# 7006268-1.net
KiCad netlist of a schematic drawn in EAGLE
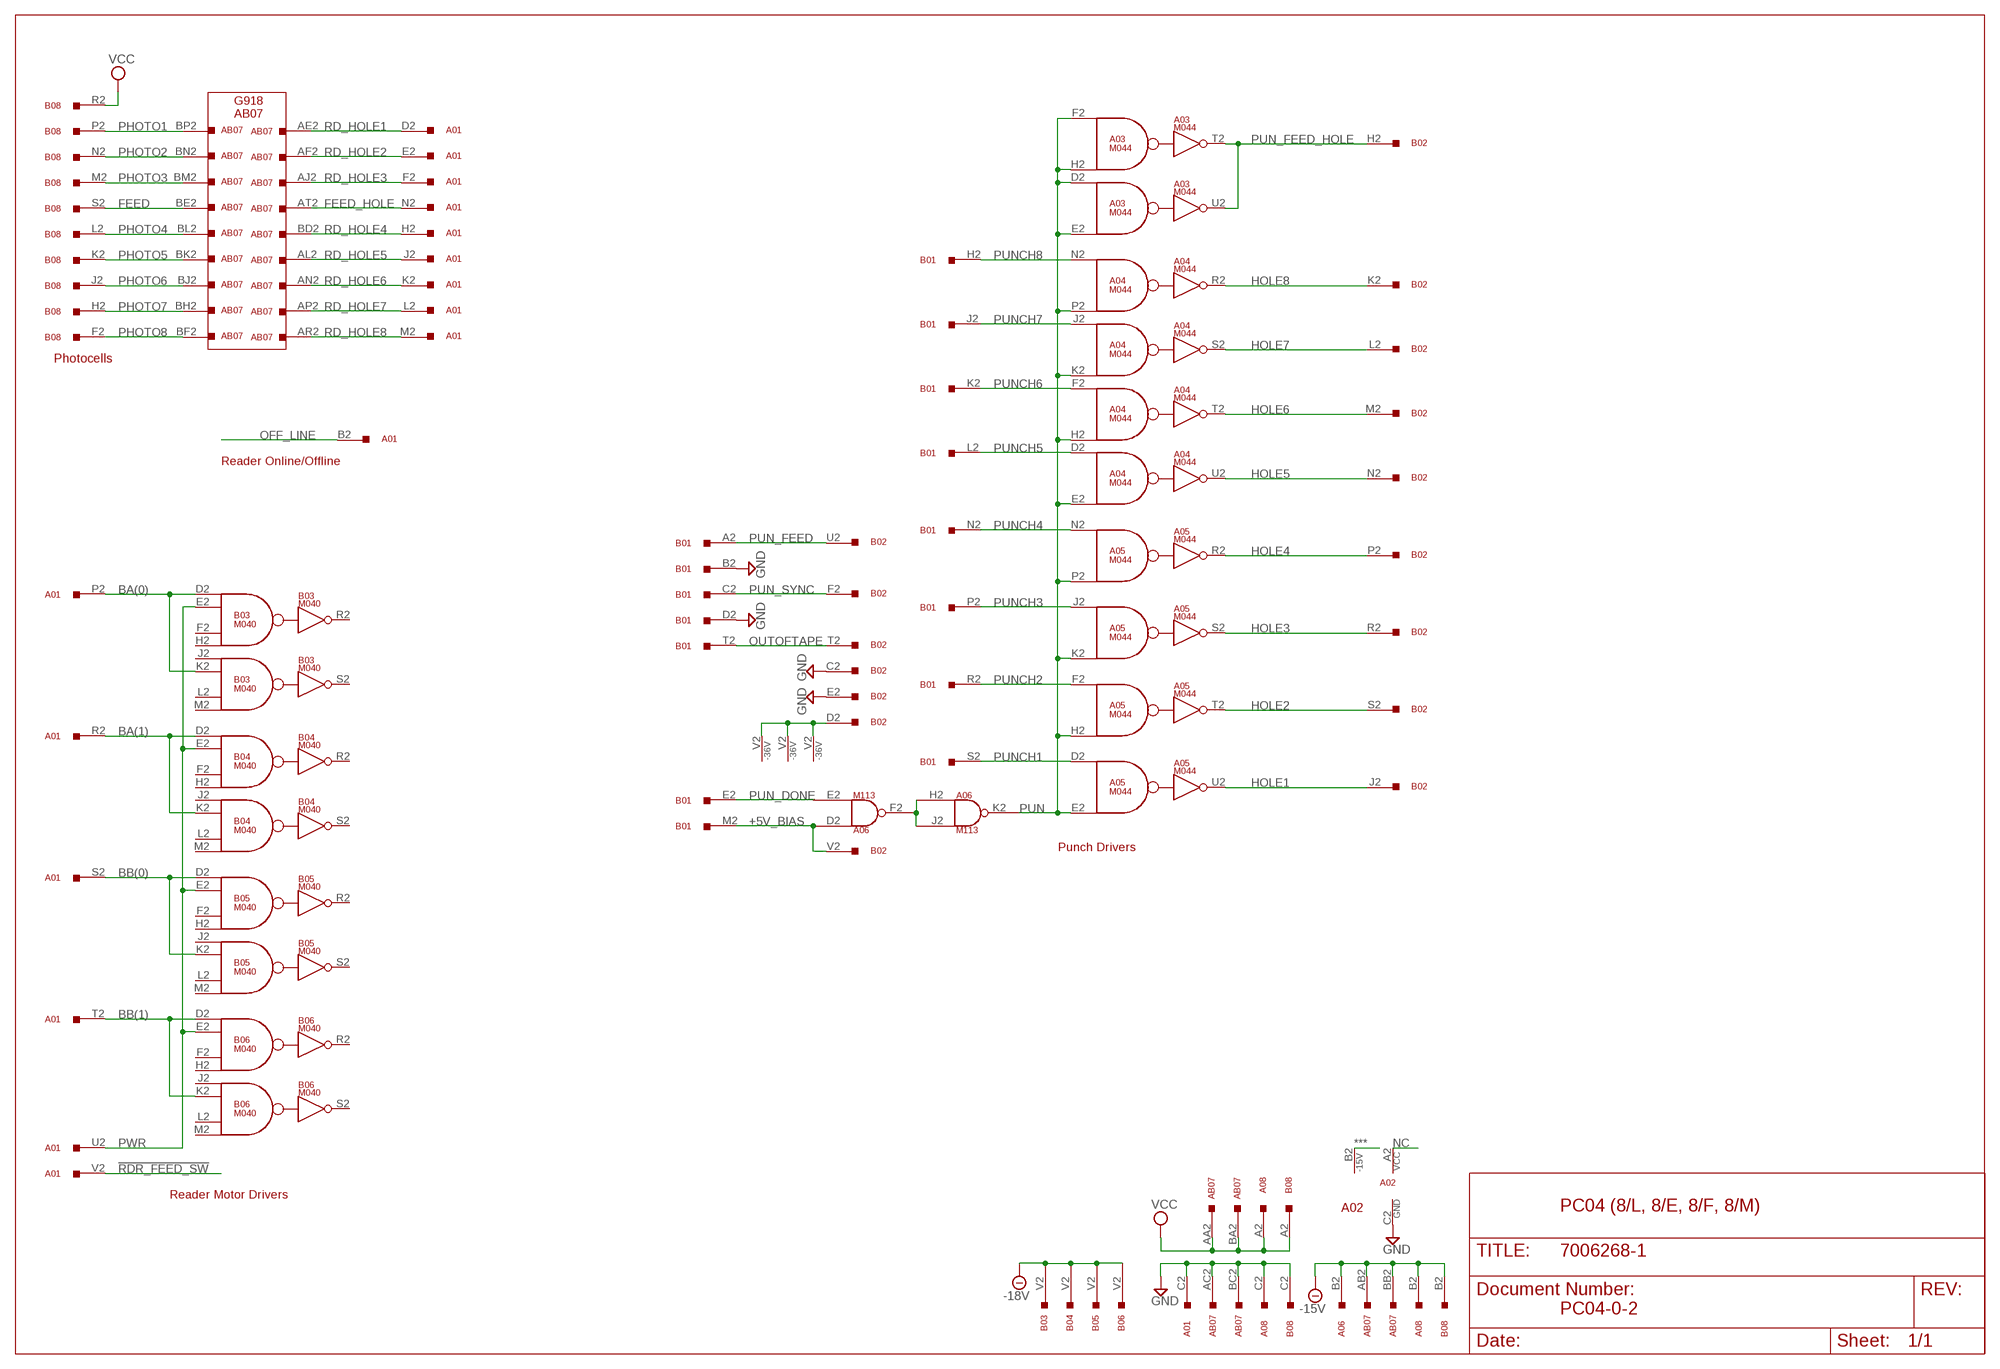
[diagram p0: schematic, sheet 1]

(export (version "E")
  (design (tool "Eeschema 10.0.6"))
  (components
    (comp (ref "A01")
      (value "W033")
      (footprint "eagle-import:H807")
      (libsource (lib "eagle-import") (part "W023"))
    )
    (comp (ref "A02")
      (value "EMPTY")
      (footprint "eagle-import:H807")
      (libsource (lib "eagle-import") (part "EMPTY"))
    )
    (comp (ref "A03")
      (value "M044")
      (footprint "eagle-import:H807")
      (libsource (lib "eagle-import") (part "M044"))
    )
    (comp (ref "A04")
      (value "M044")
      (footprint "eagle-import:H807")
      (libsource (lib "eagle-import") (part "M044"))
    )
    (comp (ref "A05")
      (value "M044")
      (footprint "eagle-import:H807")
      (libsource (lib "eagle-import") (part "M044"))
    )
    (comp (ref "A06")
      (value "M113")
      (footprint "eagle-import:H807")
      (libsource (lib "eagle-import") (part "M113"))
    )
    (comp (ref "A08")
      (value "W033")
      (footprint "eagle-import:H807")
      (libsource (lib "eagle-import") (part "W023"))
    )
    (comp (ref "AB07")
      (value "G918")
      (footprint "eagle-import:H807-2")
      (libsource (lib "eagle-import") (part "W991"))
    )
    (comp (ref "B01")
      (value "W033")
      (footprint "eagle-import:H807")
      (libsource (lib "eagle-import") (part "W023"))
    )
    (comp (ref "B02")
      (value "W033")
      (footprint "eagle-import:H807")
      (libsource (lib "eagle-import") (part "W023"))
    )
    (comp (ref "B03")
      (value "M040")
      (footprint "eagle-import:H807")
      (libsource (lib "eagle-import") (part "M040"))
    )
    (comp (ref "B04")
      (value "M040")
      (footprint "eagle-import:H807")
      (libsource (lib "eagle-import") (part "M040"))
    )
    (comp (ref "B05")
      (value "M040")
      (footprint "eagle-import:H807")
      (libsource (lib "eagle-import") (part "M040"))
    )
    (comp (ref "B06")
      (value "M040")
      (footprint "eagle-import:H807")
      (libsource (lib "eagle-import") (part "M040"))
    )
    (comp (ref "B08")
      (value "W033")
      (footprint "eagle-import:H807")
      (libsource (lib "eagle-import") (part "W023"))
    )
  )
  (nets
    (net (code "1") (name "-15V") (class "Default")
      (node (ref "A06") (pin "B2") (pinfunction "P$2_B2") (pintype "bidirectional"))
      (node (ref "A08") (pin "B2") (pinfunction "P$2_B2") (pintype "bidirectional"))
      (node (ref "AB07") (pin "AB2") (pinfunction "P$2_AB2") (pintype "bidirectional"))
      (node (ref "AB07") (pin "BB2") (pinfunction "P$2_BB2") (pintype "bidirectional"))
      (node (ref "B08") (pin "B2") (pinfunction "P$2_B2") (pintype "bidirectional"))
    )
    (net (code "2") (name "-18V") (class "Default")
      (node (ref "B03") (pin "V2") (pinfunction "P$1_V2") (pintype "input"))
      (node (ref "B04") (pin "V2") (pinfunction "P$1_V2") (pintype "input"))
      (node (ref "B05") (pin "V2") (pinfunction "P$1_V2") (pintype "input"))
      (node (ref "B06") (pin "V2") (pinfunction "P$1_V2") (pintype "input"))
    )
    (net (code "3") (name "/***") (class "Default")
      (node (ref "A02") (pin "B2") (pinfunction "-15V_B2") (pintype "power_in"))
    )
    (net (code "4") (name "/+5V_BIAS") (class "Default")
      (node (ref "A06") (pin "D2") (pinfunction "IN1_D2") (pintype "input"))
      (node (ref "B01") (pin "M2") (pinfunction "P$2_M2") (pintype "bidirectional"))
      (node (ref "B02") (pin "V2") (pinfunction "P$2_V2") (pintype "bidirectional"))
    )
    (net (code "5") (name "/BA(0)") (class "Default")
      (node (ref "A01") (pin "P2") (pinfunction "P$2_P2") (pintype "bidirectional"))
      (node (ref "B03") (pin "D2") (pinfunction "D_D2") (pintype "input"))
      (node (ref "B03") (pin "K2") (pinfunction "E_K2") (pintype "input"))
    )
    (net (code "6") (name "/BA(1)") (class "Default")
      (node (ref "A01") (pin "R2") (pinfunction "P$2_R2") (pintype "bidirectional"))
      (node (ref "B04") (pin "D2") (pinfunction "D_D2") (pintype "input"))
      (node (ref "B04") (pin "K2") (pinfunction "E_K2") (pintype "input"))
    )
    (net (code "7") (name "/BB(0)") (class "Default")
      (node (ref "A01") (pin "S2") (pinfunction "P$2_S2") (pintype "bidirectional"))
      (node (ref "B05") (pin "D2") (pinfunction "D_D2") (pintype "input"))
      (node (ref "B05") (pin "K2") (pinfunction "E_K2") (pintype "input"))
    )
    (net (code "8") (name "/BB(1)") (class "Default")
      (node (ref "A01") (pin "T2") (pinfunction "P$2_T2") (pintype "bidirectional"))
      (node (ref "B06") (pin "D2") (pinfunction "D_D2") (pintype "input"))
      (node (ref "B06") (pin "K2") (pinfunction "E_K2") (pintype "input"))
    )
    (net (code "9") (name "/FEED") (class "Default")
      (node (ref "AB07") (pin "BE2") (pinfunction "P$2_BE2") (pintype "bidirectional"))
      (node (ref "B08") (pin "S2") (pinfunction "P$2_S2") (pintype "bidirectional"))
    )
    (net (code "10") (name "/FEED_HOLE") (class "Default")
      (node (ref "A01") (pin "N2") (pinfunction "P$2_N2") (pintype "bidirectional"))
      (node (ref "AB07") (pin "AT2") (pinfunction "P$2_AT2") (pintype "bidirectional"))
    )
    (net (code "11") (name "/HOLE1") (class "Default")
      (node (ref "A05") (pin "U2") (pinfunction "R_U2") (pintype "open_collector"))
      (node (ref "B02") (pin "J2") (pinfunction "P$2_J2") (pintype "bidirectional"))
    )
    (net (code "12") (name "/HOLE2") (class "Default")
      (node (ref "A05") (pin "T2") (pinfunction "R_T2") (pintype "open_collector"))
      (node (ref "B02") (pin "S2") (pinfunction "P$2_S2") (pintype "bidirectional"))
    )
    (net (code "13") (name "/HOLE3") (class "Default")
      (node (ref "A05") (pin "S2") (pinfunction "R_S2") (pintype "open_collector"))
      (node (ref "B02") (pin "R2") (pinfunction "P$2_R2") (pintype "bidirectional"))
    )
    (net (code "14") (name "/HOLE4") (class "Default")
      (node (ref "A05") (pin "R2") (pinfunction "R_R2") (pintype "open_collector"))
      (node (ref "B02") (pin "P2") (pinfunction "P$2_P2") (pintype "bidirectional"))
    )
    (net (code "15") (name "/HOLE5") (class "Default")
      (node (ref "A04") (pin "U2") (pinfunction "R_U2") (pintype "open_collector"))
      (node (ref "B02") (pin "N2") (pinfunction "P$2_N2") (pintype "bidirectional"))
    )
    (net (code "16") (name "/HOLE6") (class "Default")
      (node (ref "A04") (pin "T2") (pinfunction "R_T2") (pintype "open_collector"))
      (node (ref "B02") (pin "M2") (pinfunction "P$2_M2") (pintype "bidirectional"))
    )
    (net (code "17") (name "/HOLE7") (class "Default")
      (node (ref "A04") (pin "S2") (pinfunction "R_S2") (pintype "open_collector"))
      (node (ref "B02") (pin "L2") (pinfunction "P$2_L2") (pintype "bidirectional"))
    )
    (net (code "18") (name "/HOLE8") (class "Default")
      (node (ref "A04") (pin "R2") (pinfunction "R_R2") (pintype "open_collector"))
      (node (ref "B02") (pin "K2") (pinfunction "P$2_K2") (pintype "bidirectional"))
    )
    (net (code "19") (name "/NC") (class "Default")
      (node (ref "A02") (pin "A2") (pinfunction "VCC_A2") (pintype "power_in"))
    )
    (net (code "20") (name "/OFF_LINE") (class "Default")
      (node (ref "A01") (pin "B2") (pinfunction "P$2_B2") (pintype "bidirectional"))
    )
    (net (code "21") (name "/OUTOFTAPE") (class "Default")
      (node (ref "B01") (pin "T2") (pinfunction "P$2_T2") (pintype "bidirectional"))
      (node (ref "B02") (pin "T2") (pinfunction "P$2_T2") (pintype "bidirectional"))
    )
    (net (code "22") (name "/PHOTO1") (class "Default")
      (node (ref "AB07") (pin "BP2") (pinfunction "P$2_BP2") (pintype "bidirectional"))
      (node (ref "B08") (pin "P2") (pinfunction "P$2_P2") (pintype "bidirectional"))
    )
    (net (code "23") (name "/PHOTO2") (class "Default")
      (node (ref "AB07") (pin "BN2") (pinfunction "P$2_BN2") (pintype "bidirectional"))
      (node (ref "B08") (pin "N2") (pinfunction "P$2_N2") (pintype "bidirectional"))
    )
    (net (code "24") (name "/PHOTO3") (class "Default")
      (node (ref "AB07") (pin "BM2") (pinfunction "P$2_BM2") (pintype "bidirectional"))
      (node (ref "B08") (pin "M2") (pinfunction "P$2_M2") (pintype "bidirectional"))
    )
    (net (code "25") (name "/PHOTO4") (class "Default")
      (node (ref "AB07") (pin "BL2") (pinfunction "P$2_BL2") (pintype "bidirectional"))
      (node (ref "B08") (pin "L2") (pinfunction "P$2_L2") (pintype "bidirectional"))
    )
    (net (code "26") (name "/PHOTO5") (class "Default")
      (node (ref "AB07") (pin "BK2") (pinfunction "P$2_BK2") (pintype "bidirectional"))
      (node (ref "B08") (pin "K2") (pinfunction "P$2_K2") (pintype "bidirectional"))
    )
    (net (code "27") (name "/PHOTO6") (class "Default")
      (node (ref "AB07") (pin "BJ2") (pinfunction "P$2_BJ2") (pintype "bidirectional"))
      (node (ref "B08") (pin "J2") (pinfunction "P$2_J2") (pintype "bidirectional"))
    )
    (net (code "28") (name "/PHOTO7") (class "Default")
      (node (ref "AB07") (pin "BH2") (pinfunction "P$2_BH2") (pintype "bidirectional"))
      (node (ref "B08") (pin "H2") (pinfunction "P$2_H2") (pintype "bidirectional"))
    )
    (net (code "29") (name "/PHOTO8") (class "Default")
      (node (ref "AB07") (pin "BF2") (pinfunction "P$2_BF2") (pintype "bidirectional"))
      (node (ref "B08") (pin "F2") (pinfunction "P$2_F2") (pintype "bidirectional"))
    )
    (net (code "30") (name "/PUN") (class "Default")
      (node (ref "A03") (pin "D2") (pinfunction "D_D2") (pintype "input"))
      (node (ref "A03") (pin "E2") (pinfunction "H_E2") (pintype "input"))
      (node (ref "A03") (pin "F2") (pinfunction "D_F2") (pintype "input"))
      (node (ref "A03") (pin "H2") (pinfunction "H_H2") (pintype "input"))
      (node (ref "A04") (pin "E2") (pinfunction "H_E2") (pintype "input"))
      (node (ref "A04") (pin "H2") (pinfunction "H_H2") (pintype "input"))
      (node (ref "A04") (pin "K2") (pinfunction "H_K2") (pintype "input"))
      (node (ref "A04") (pin "P2") (pinfunction "H_P2") (pintype "input"))
      (node (ref "A05") (pin "E2") (pinfunction "H_E2") (pintype "input"))
      (node (ref "A05") (pin "H2") (pinfunction "H_H2") (pintype "input"))
      (node (ref "A05") (pin "K2") (pinfunction "H_K2") (pintype "input"))
      (node (ref "A05") (pin "P2") (pinfunction "H_P2") (pintype "input"))
      (node (ref "A06") (pin "K2") (pinfunction "OUT_K2") (pintype "output"))
    )
    (net (code "31") (name "/PUNCH1") (class "Default")
      (node (ref "A05") (pin "D2") (pinfunction "D_D2") (pintype "input"))
      (node (ref "B01") (pin "S2") (pinfunction "P$2_S2") (pintype "bidirectional"))
    )
    (net (code "32") (name "/PUNCH2") (class "Default")
      (node (ref "A05") (pin "F2") (pinfunction "D_F2") (pintype "input"))
      (node (ref "B01") (pin "R2") (pinfunction "P$2_R2") (pintype "bidirectional"))
    )
    (net (code "33") (name "/PUNCH3") (class "Default")
      (node (ref "A05") (pin "J2") (pinfunction "D_J2") (pintype "input"))
      (node (ref "B01") (pin "P2") (pinfunction "P$2_P2") (pintype "bidirectional"))
    )
    (net (code "34") (name "/PUNCH4") (class "Default")
      (node (ref "A05") (pin "N2") (pinfunction "D_N2") (pintype "input"))
      (node (ref "B01") (pin "N2") (pinfunction "P$2_N2") (pintype "bidirectional"))
    )
    (net (code "35") (name "/PUNCH5") (class "Default")
      (node (ref "A04") (pin "D2") (pinfunction "D_D2") (pintype "input"))
      (node (ref "B01") (pin "L2") (pinfunction "P$2_L2") (pintype "bidirectional"))
    )
    (net (code "36") (name "/PUNCH6") (class "Default")
      (node (ref "A04") (pin "F2") (pinfunction "D_F2") (pintype "input"))
      (node (ref "B01") (pin "K2") (pinfunction "P$2_K2") (pintype "bidirectional"))
    )
    (net (code "37") (name "/PUNCH7") (class "Default")
      (node (ref "A04") (pin "J2") (pinfunction "D_J2") (pintype "input"))
      (node (ref "B01") (pin "J2") (pinfunction "P$2_J2") (pintype "bidirectional"))
    )
    (net (code "38") (name "/PUNCH8") (class "Default")
      (node (ref "A04") (pin "N2") (pinfunction "D_N2") (pintype "input"))
      (node (ref "B01") (pin "H2") (pinfunction "P$2_H2") (pintype "bidirectional"))
    )
    (net (code "39") (name "/PUN_DONE") (class "Default")
      (node (ref "A06") (pin "E2") (pinfunction "IN2_E2") (pintype "input"))
      (node (ref "B01") (pin "E2") (pinfunction "P$2_E2") (pintype "bidirectional"))
    )
    (net (code "40") (name "/PUN_FEED") (class "Default")
      (node (ref "B01") (pin "A2") (pinfunction "P$2_A2") (pintype "bidirectional"))
      (node (ref "B02") (pin "U2") (pinfunction "P$2_U2") (pintype "bidirectional"))
    )
    (net (code "41") (name "/PUN_FEED_HOLE") (class "Default")
      (node (ref "A03") (pin "T2") (pinfunction "R_T2") (pintype "open_collector"))
      (node (ref "A03") (pin "U2") (pinfunction "R_U2") (pintype "open_collector"))
      (node (ref "B02") (pin "H2") (pinfunction "P$2_H2") (pintype "bidirectional"))
    )
    (net (code "42") (name "/PUN_SYNC") (class "Default")
      (node (ref "B01") (pin "C2") (pinfunction "P$2_C2") (pintype "bidirectional"))
      (node (ref "B02") (pin "F2") (pinfunction "P$2_F2") (pintype "bidirectional"))
    )
    (net (code "43") (name "/PWR") (class "Default")
      (node (ref "A01") (pin "U2") (pinfunction "P$2_U2") (pintype "bidirectional"))
      (node (ref "B03") (pin "E2") (pinfunction "E_E2") (pintype "input"))
      (node (ref "B04") (pin "E2") (pinfunction "E_E2") (pintype "input"))
      (node (ref "B05") (pin "E2") (pinfunction "E_E2") (pintype "input"))
      (node (ref "B06") (pin "E2") (pinfunction "E_E2") (pintype "input"))
    )
    (net (code "44") (name "/RD_HOLE1") (class "Default")
      (node (ref "A01") (pin "D2") (pinfunction "P$2_D2") (pintype "bidirectional"))
      (node (ref "AB07") (pin "AE2") (pinfunction "P$2_AE2") (pintype "bidirectional"))
    )
    (net (code "45") (name "/RD_HOLE2") (class "Default")
      (node (ref "A01") (pin "E2") (pinfunction "P$2_E2") (pintype "bidirectional"))
      (node (ref "AB07") (pin "AF2") (pinfunction "P$2_AF2") (pintype "bidirectional"))
    )
    (net (code "46") (name "/RD_HOLE3") (class "Default")
      (node (ref "A01") (pin "F2") (pinfunction "P$2_F2") (pintype "bidirectional"))
      (node (ref "AB07") (pin "AJ2") (pinfunction "P$2_AJ2") (pintype "bidirectional"))
    )
    (net (code "47") (name "/RD_HOLE4") (class "Default")
      (node (ref "A01") (pin "H2") (pinfunction "P$2_H2") (pintype "bidirectional"))
      (node (ref "AB07") (pin "BD2") (pinfunction "P$2_BD2") (pintype "bidirectional"))
    )
    (net (code "48") (name "/RD_HOLE5") (class "Default")
      (node (ref "A01") (pin "J2") (pinfunction "P$2_J2") (pintype "bidirectional"))
      (node (ref "AB07") (pin "AL2") (pinfunction "P$2_AL2") (pintype "bidirectional"))
    )
    (net (code "49") (name "/RD_HOLE6") (class "Default")
      (node (ref "A01") (pin "K2") (pinfunction "P$2_K2") (pintype "bidirectional"))
      (node (ref "AB07") (pin "AN2") (pinfunction "P$2_AN2") (pintype "bidirectional"))
    )
    (net (code "50") (name "/RD_HOLE7") (class "Default")
      (node (ref "A01") (pin "L2") (pinfunction "P$2_L2") (pintype "bidirectional"))
      (node (ref "AB07") (pin "AP2") (pinfunction "P$2_AP2") (pintype "bidirectional"))
    )
    (net (code "51") (name "/RD_HOLE8") (class "Default")
      (node (ref "A01") (pin "M2") (pinfunction "P$2_M2") (pintype "bidirectional"))
      (node (ref "AB07") (pin "AR2") (pinfunction "P$2_AR2") (pintype "bidirectional"))
    )
    (net (code "52") (name "/~{RDR_FEED_SW}") (class "Default")
      (node (ref "A01") (pin "V2") (pinfunction "P$2_V2") (pintype "bidirectional"))
    )
    (net (code "53") (name "GND") (class "Default")
      (node (ref "A01") (pin "C2") (pinfunction "P$2_C2") (pintype "bidirectional"))
      (node (ref "A02") (pin "C2") (pinfunction "GND_C2") (pintype "power_in"))
      (node (ref "A08") (pin "C2") (pinfunction "P$2_C2") (pintype "bidirectional"))
      (node (ref "AB07") (pin "AC2") (pinfunction "P$2_AC2") (pintype "bidirectional"))
      (node (ref "AB07") (pin "BC2") (pinfunction "P$2_BC2") (pintype "bidirectional"))
      (node (ref "B01") (pin "B2") (pinfunction "P$2_B2") (pintype "bidirectional"))
      (node (ref "B01") (pin "D2") (pinfunction "P$2_D2") (pintype "bidirectional"))
      (node (ref "B02") (pin "C2") (pinfunction "P$2_C2") (pintype "bidirectional"))
      (node (ref "B02") (pin "E2") (pinfunction "P$2_E2") (pintype "bidirectional"))
      (node (ref "B08") (pin "C2") (pinfunction "P$2_C2") (pintype "bidirectional"))
    )
    (net (code "54") (name "Net-(A03G--36V)") (class "Default")
      (node (ref "A03") (pin "V2") (pinfunction "-36V_V2") (pintype "power_in"))
      (node (ref "A04") (pin "V2") (pinfunction "-36V_V2") (pintype "power_in"))
      (node (ref "A05") (pin "V2") (pinfunction "-36V_V2") (pintype "power_in"))
      (node (ref "B02") (pin "D2") (pinfunction "P$2_D2") (pintype "bidirectional"))
    )
    (net (code "55") (name "Net-(A06D-OUT)") (class "Default")
      (node (ref "A06") (pin "F2") (pinfunction "OUT_F2") (pintype "output"))
      (node (ref "A06") (pin "H2") (pinfunction "IN1_H2") (pintype "input"))
      (node (ref "A06") (pin "J2") (pinfunction "IN2_J2") (pintype "input"))
    )
    (net (code "56") (name "VCC") (class "Default")
      (node (ref "A08") (pin "A2") (pinfunction "P$2_A2") (pintype "bidirectional"))
      (node (ref "AB07") (pin "AA2") (pinfunction "P$2_AA2") (pintype "bidirectional"))
      (node (ref "AB07") (pin "BA2") (pinfunction "P$2_BA2") (pintype "bidirectional"))
      (node (ref "B08") (pin "A2") (pinfunction "P$2_A2") (pintype "bidirectional"))
      (node (ref "B08") (pin "R2") (pinfunction "P$2_R2") (pintype "bidirectional"))
    )
    (net (code "57") (name "unconnected-(B03A-F-PadF2)") (class "Default")
      (node (ref "B03") (pin "F2") (pinfunction "F_F2") (pintype "input"))
    )
    (net (code "58") (name "unconnected-(B03A-H-PadH2)") (class "Default")
      (node (ref "B03") (pin "H2") (pinfunction "H_H2") (pintype "input"))
    )
    (net (code "59") (name "unconnected-(B03A-R-PadR2)") (class "Default")
      (node (ref "B03") (pin "R2") (pinfunction "R_R2") (pintype "open_collector"))
    )
    (net (code "60") (name "unconnected-(B03B-D-PadJ2)") (class "Default")
      (node (ref "B03") (pin "J2") (pinfunction "D_J2") (pintype "input"))
    )
    (net (code "61") (name "unconnected-(B03B-F-PadL2)") (class "Default")
      (node (ref "B03") (pin "L2") (pinfunction "F_L2") (pintype "input"))
    )
    (net (code "62") (name "unconnected-(B03B-H-PadM2)") (class "Default")
      (node (ref "B03") (pin "M2") (pinfunction "H_M2") (pintype "input"))
    )
    (net (code "63") (name "unconnected-(B03B-R-PadS2)") (class "Default")
      (node (ref "B03") (pin "S2") (pinfunction "R_S2") (pintype "open_collector"))
    )
    (net (code "64") (name "unconnected-(B04A-F-PadF2)") (class "Default")
      (node (ref "B04") (pin "F2") (pinfunction "F_F2") (pintype "input"))
    )
    (net (code "65") (name "unconnected-(B04A-H-PadH2)") (class "Default")
      (node (ref "B04") (pin "H2") (pinfunction "H_H2") (pintype "input"))
    )
    (net (code "66") (name "unconnected-(B04A-R-PadR2)") (class "Default")
      (node (ref "B04") (pin "R2") (pinfunction "R_R2") (pintype "open_collector"))
    )
    (net (code "67") (name "unconnected-(B04B-D-PadJ2)") (class "Default")
      (node (ref "B04") (pin "J2") (pinfunction "D_J2") (pintype "input"))
    )
    (net (code "68") (name "unconnected-(B04B-F-PadL2)") (class "Default")
      (node (ref "B04") (pin "L2") (pinfunction "F_L2") (pintype "input"))
    )
    (net (code "69") (name "unconnected-(B04B-H-PadM2)") (class "Default")
      (node (ref "B04") (pin "M2") (pinfunction "H_M2") (pintype "input"))
    )
    (net (code "70") (name "unconnected-(B04B-R-PadS2)") (class "Default")
      (node (ref "B04") (pin "S2") (pinfunction "R_S2") (pintype "open_collector"))
    )
    (net (code "71") (name "unconnected-(B05A-F-PadF2)") (class "Default")
      (node (ref "B05") (pin "F2") (pinfunction "F_F2") (pintype "input"))
    )
    (net (code "72") (name "unconnected-(B05A-H-PadH2)") (class "Default")
      (node (ref "B05") (pin "H2") (pinfunction "H_H2") (pintype "input"))
    )
    (net (code "73") (name "unconnected-(B05A-R-PadR2)") (class "Default")
      (node (ref "B05") (pin "R2") (pinfunction "R_R2") (pintype "open_collector"))
    )
    (net (code "74") (name "unconnected-(B05B-D-PadJ2)") (class "Default")
      (node (ref "B05") (pin "J2") (pinfunction "D_J2") (pintype "input"))
    )
    (net (code "75") (name "unconnected-(B05B-F-PadL2)") (class "Default")
      (node (ref "B05") (pin "L2") (pinfunction "F_L2") (pintype "input"))
    )
    (net (code "76") (name "unconnected-(B05B-H-PadM2)") (class "Default")
      (node (ref "B05") (pin "M2") (pinfunction "H_M2") (pintype "input"))
    )
    (net (code "77") (name "unconnected-(B05B-R-PadS2)") (class "Default")
      (node (ref "B05") (pin "S2") (pinfunction "R_S2") (pintype "open_collector"))
    )
    (net (code "78") (name "unconnected-(B06A-F-PadF2)") (class "Default")
      (node (ref "B06") (pin "F2") (pinfunction "F_F2") (pintype "input"))
    )
    (net (code "79") (name "unconnected-(B06A-H-PadH2)") (class "Default")
      (node (ref "B06") (pin "H2") (pinfunction "H_H2") (pintype "input"))
    )
    (net (code "80") (name "unconnected-(B06A-R-PadR2)") (class "Default")
      (node (ref "B06") (pin "R2") (pinfunction "R_R2") (pintype "open_collector"))
    )
    (net (code "81") (name "unconnected-(B06B-D-PadJ2)") (class "Default")
      (node (ref "B06") (pin "J2") (pinfunction "D_J2") (pintype "input"))
    )
    (net (code "82") (name "unconnected-(B06B-F-PadL2)") (class "Default")
      (node (ref "B06") (pin "L2") (pinfunction "F_L2") (pintype "input"))
    )
    (net (code "83") (name "unconnected-(B06B-H-PadM2)") (class "Default")
      (node (ref "B06") (pin "M2") (pinfunction "H_M2") (pintype "input"))
    )
    (net (code "84") (name "unconnected-(B06B-R-PadS2)") (class "Default")
      (node (ref "B06") (pin "S2") (pinfunction "R_S2") (pintype "open_collector"))
    )
  )
)
